# SH4_-_3_3V_LINEAR_REGULATOR.net
KiCad netlist of a schematic drawn in Altium Designer
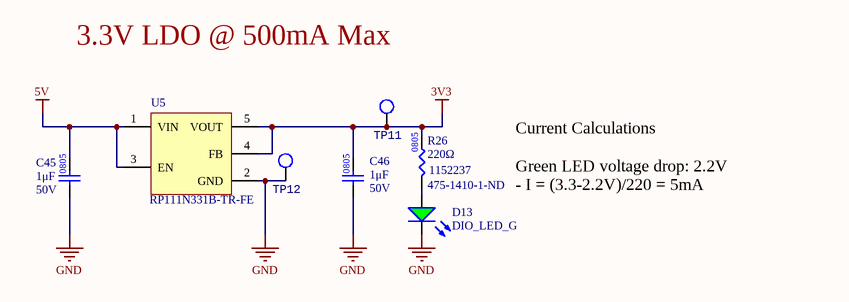
[diagram p0: SH4 - 3.3V LINEAR REGULATOR.SchDoc]

(export (version "E")
  (design (tool "Eeschema 10.0.6"))
  (components
    (comp (ref "C45")
      (value "1μF")
      (footprint "CAP2012")
      (description "CAP CER 1UF 50V X7R 0805")
      (fields
        (field (name "VOLTAGE RATING") "50V")
        (field (name "LCSC PART #") "C28323")
        (field (name "Comment") "CAP_1uF_50V_0805")
      )
      (libsource (lib "UWRT_Schematic_Library_2020") (part "CAP_1uF_50V_0805"))
    )
    (comp (ref "C46")
      (value "1μF")
      (footprint "CAP2012")
      (description "CAP CER 1UF 50V X7R 0805")
      (fields
        (field (name "VOLTAGE RATING") "50V")
        (field (name "LCSC PART #") "C28323")
        (field (name "Comment") "CAP_1uF_50V_0805")
      )
      (libsource (lib "UWRT_Schematic_Library_2020") (part "CAP_1uF_50V_0805"))
    )
    (comp (ref "D13")
      (value "DIO_LED_G")
      (footprint "LED_0805_GREEN")
      (description "LED GREEN DIFFUSED 0805 SMD")
      (fields
        (field (name "SUPPLIER PART NUMBER 1") "475-1410-1-ND")
        (field (name "SUPPLIER PART NUMBER 2") "1152237")
      )
      (libsource (lib "UWRT_Schematic_Library_2020") (part "DIO_LED_G"))
    )
    (comp (ref "R26")
      (value "220Ω")
      (footprint "RES0805")
      (description "RES 220 OHM 5% 1/2W 0805")
      (fields (field (name "LCSC PART #") "C17557") (field (name "Comment") "RES_220Ω_0805_5%"))
      (libsource (lib "UWRT_Schematic_Library_2020") (part "RES_220Ω_0805_5%"))
    )
    (comp (ref "TP11")
      (value "TESTPOINT_LOOP")
      (footprint "TESTPOINT_LOOP")
      (description "TESTPOINT THRUHOLE")
      (libsource (lib "UWRT_Schematic_Library_2020") (part "TESTPOINT_LOOP"))
    )
    (comp (ref "TP12")
      (value "TESTPOINT_LOOP")
      (footprint "TESTPOINT_LOOP")
      (description "TESTPOINT THRUHOLE")
      (libsource (lib "UWRT_Schematic_Library_2020") (part "TESTPOINT_LOOP"))
    )
    (comp (ref "U5")
      (value "LDO_3.3V_500mA")
      (footprint "SOT23-5")
      (description "IC REG LINEAR 3.3V 500MA SOT23-5")
      (fields (field (name "MANUFACTURER PART NUMBER 1") "RP111N331B-TR-FE"))
      (libsource (lib "UWRT_Schematic_Library_2020") (part "LDO_3.3V_500mA"))
    )
  )
  (nets
    (net (code "1") (name "3V3") (class "Default")
      (node (ref "C46") (pin "2") (pinfunction "2_2") (pintype "passive"))
      (node (ref "R26") (pin "2") (pinfunction "2_2") (pintype "passive"))
      (node (ref "TP11") (pin "1") (pintype "passive"))
      (node (ref "U5") (pin "4") (pinfunction "FB_4") (pintype "passive"))
      (node (ref "U5") (pin "5") (pinfunction "VOUT_5") (pintype "passive"))
    )
    (net (code "2") (name "5V") (class "Default")
      (node (ref "C45") (pin "2") (pinfunction "2_2") (pintype "passive"))
      (node (ref "U5") (pin "1") (pinfunction "VIN_1") (pintype "passive"))
      (node (ref "U5") (pin "3") (pinfunction "EN_3") (pintype "passive"))
    )
    (net (code "3") (name "GND") (class "Default")
      (node (ref "C45") (pin "1") (pinfunction "1_1") (pintype "passive"))
      (node (ref "C46") (pin "1") (pinfunction "1_1") (pintype "passive"))
      (node (ref "D13") (pin "2") (pinfunction "K_2") (pintype "passive"))
      (node (ref "TP12") (pin "1") (pintype "passive"))
      (node (ref "U5") (pin "2") (pinfunction "GND_2") (pintype "passive"))
    )
    (net (code "4") (name "Net-(D13-A)") (class "Default")
      (node (ref "D13") (pin "1") (pinfunction "A_1") (pintype "passive"))
      (node (ref "R26") (pin "1") (pinfunction "1_1") (pintype "passive"))
    )
  )
)
